# ade_7753.net
KiCad netlist of a schematic drawn in EAGLE
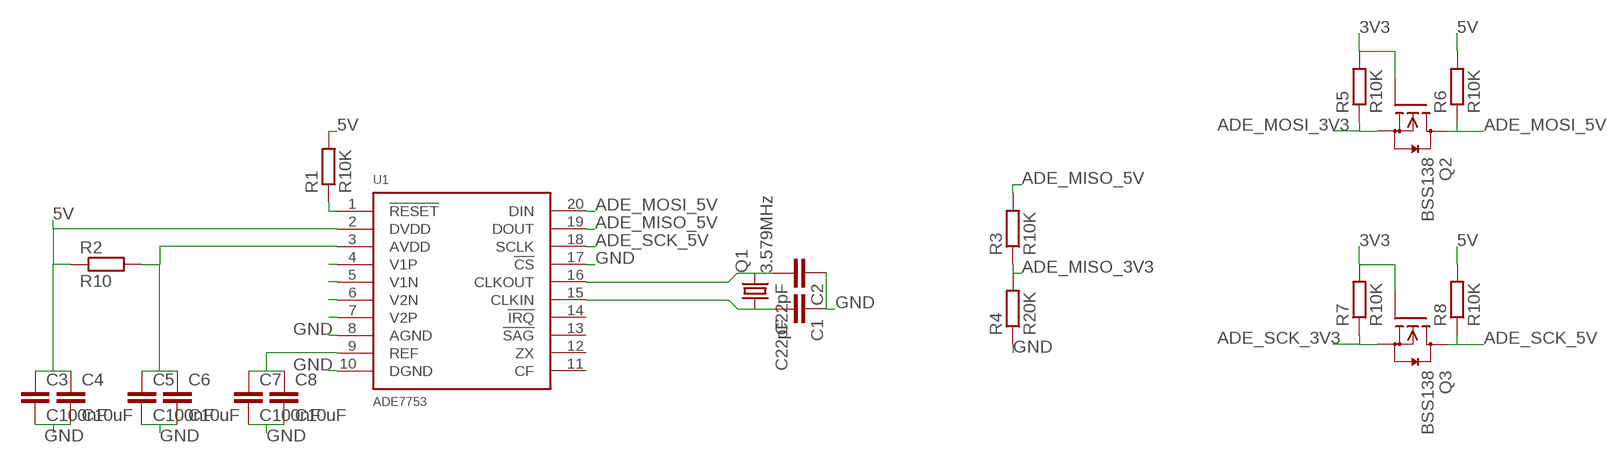
[diagram p0: schematic, sheet 1]

(export (version "E")
  (design (tool "Eeschema 10.0.6"))
  (components
    (comp (ref "C1")
      (value "C22pF")
      (footprint "eagle-import:C0805")
      (libsource (lib "eagle-import") (part "C-EUC0805"))
    )
    (comp (ref "C2")
      (value "C22pF")
      (footprint "eagle-import:C0805")
      (libsource (lib "eagle-import") (part "C-EUC0805"))
    )
    (comp (ref "C3")
      (value "C100nF")
      (footprint "eagle-import:C0805")
      (libsource (lib "eagle-import") (part "C-EUC0805"))
    )
    (comp (ref "C4")
      (value "C10uF")
      (footprint "eagle-import:C0805")
      (libsource (lib "eagle-import") (part "C-EUC0805"))
    )
    (comp (ref "C5")
      (value "C100nF")
      (footprint "eagle-import:C0805")
      (libsource (lib "eagle-import") (part "C-EUC0805"))
    )
    (comp (ref "C6")
      (value "C10uF")
      (footprint "eagle-import:C0805")
      (libsource (lib "eagle-import") (part "C-EUC0805"))
    )
    (comp (ref "C7")
      (value "C100nF")
      (footprint "eagle-import:C0805")
      (libsource (lib "eagle-import") (part "C-EUC0805"))
    )
    (comp (ref "C8")
      (value "C10uF")
      (footprint "eagle-import:C0805")
      (libsource (lib "eagle-import") (part "C-EUC0805"))
    )
    (comp (ref "Q1")
      (value "3.579MHz")
      (footprint "eagle-import:HC49_S")
      (libsource (lib "eagle-import") (part "CRYSTALHC49S"))
    )
    (comp (ref "Q2")
      (value "BSS138")
      (footprint "eagle-import:SOT23")
      (libsource (lib "eagle-import") (part "BSS138"))
    )
    (comp (ref "Q3")
      (value "BSS138")
      (footprint "eagle-import:SOT23")
      (libsource (lib "eagle-import") (part "BSS138"))
    )
    (comp (ref "R1")
      (value "R10K")
      (footprint "eagle-import:M0805")
      (libsource (lib "eagle-import") (part "R-EU_M0805"))
    )
    (comp (ref "R2")
      (value "R10")
      (footprint "eagle-import:M0805")
      (libsource (lib "eagle-import") (part "R-EU_M0805"))
    )
    (comp (ref "R3")
      (value "R10K")
      (footprint "eagle-import:M0805")
      (libsource (lib "eagle-import") (part "R-EU_M0805"))
    )
    (comp (ref "R4")
      (value "R20K")
      (footprint "eagle-import:M0805")
      (libsource (lib "eagle-import") (part "R-EU_M0805"))
    )
    (comp (ref "R5")
      (value "R10K")
      (footprint "eagle-import:M0805")
      (libsource (lib "eagle-import") (part "R-EU_M0805"))
    )
    (comp (ref "R6")
      (value "R10K")
      (footprint "eagle-import:M0805")
      (libsource (lib "eagle-import") (part "R-EU_M0805"))
    )
    (comp (ref "R7")
      (value "R10K")
      (footprint "eagle-import:M0805")
      (libsource (lib "eagle-import") (part "R-EU_M0805"))
    )
    (comp (ref "R8")
      (value "R10K")
      (footprint "eagle-import:M0805")
      (libsource (lib "eagle-import") (part "R-EU_M0805"))
    )
    (comp (ref "U1")
      (value "ADE7753")
      (footprint "eagle-import:SSOP-20")
      (libsource (lib "eagle-import") (part "ADE7753"))
    )
  )
  (nets
    (net (code "1") (name "/3V3") (class "Default")
      (node (ref "Q2") (pin "1") (pinfunction "G_1") (pintype "passive"))
      (node (ref "Q3") (pin "1") (pinfunction "G_1") (pintype "passive"))
      (node (ref "R5") (pin "2") (pinfunction "2_2") (pintype "passive"))
      (node (ref "R7") (pin "2") (pinfunction "2_2") (pintype "passive"))
    )
    (net (code "2") (name "/5V") (class "Default")
      (node (ref "C3") (pin "1") (pinfunction "1_1") (pintype "passive"))
      (node (ref "C4") (pin "1") (pinfunction "1_1") (pintype "passive"))
      (node (ref "R1") (pin "2") (pinfunction "2_2") (pintype "passive"))
      (node (ref "R2") (pin "1") (pinfunction "1_1") (pintype "passive"))
      (node (ref "R6") (pin "2") (pinfunction "2_2") (pintype "passive"))
      (node (ref "R8") (pin "2") (pinfunction "2_2") (pintype "passive"))
      (node (ref "U1") (pin "2") (pinfunction "DVDD_2") (pintype "bidirectional"))
    )
    (net (code "3") (name "/ADE_MISO_3V3") (class "Default")
      (node (ref "R3") (pin "1") (pinfunction "1_1") (pintype "passive"))
      (node (ref "R4") (pin "2") (pinfunction "2_2") (pintype "passive"))
    )
    (net (code "4") (name "/ADE_MISO_5V") (class "Default")
      (node (ref "R3") (pin "2") (pinfunction "2_2") (pintype "passive"))
      (node (ref "U1") (pin "19") (pinfunction "DOUT_19") (pintype "bidirectional"))
    )
    (net (code "5") (name "/ADE_MOSI_3V3") (class "Default")
      (node (ref "Q2") (pin "2") (pinfunction "S_2") (pintype "passive"))
      (node (ref "R5") (pin "1") (pinfunction "1_1") (pintype "passive"))
    )
    (net (code "6") (name "/ADE_MOSI_5V") (class "Default")
      (node (ref "Q2") (pin "3") (pinfunction "D_3") (pintype "passive"))
      (node (ref "R6") (pin "1") (pinfunction "1_1") (pintype "passive"))
      (node (ref "U1") (pin "20") (pinfunction "DIN_20") (pintype "bidirectional"))
    )
    (net (code "7") (name "/ADE_SCK_3V3") (class "Default")
      (node (ref "Q3") (pin "2") (pinfunction "S_2") (pintype "passive"))
      (node (ref "R7") (pin "1") (pinfunction "1_1") (pintype "passive"))
    )
    (net (code "8") (name "/ADE_SCK_5V") (class "Default")
      (node (ref "Q3") (pin "3") (pinfunction "D_3") (pintype "passive"))
      (node (ref "R8") (pin "1") (pinfunction "1_1") (pintype "passive"))
      (node (ref "U1") (pin "18") (pinfunction "SCLK_18") (pintype "bidirectional"))
    )
    (net (code "9") (name "/GND") (class "Default")
      (node (ref "C1") (pin "1") (pinfunction "1_1") (pintype "passive"))
      (node (ref "C2") (pin "1") (pinfunction "1_1") (pintype "passive"))
      (node (ref "C3") (pin "2") (pinfunction "2_2") (pintype "passive"))
      (node (ref "C4") (pin "2") (pinfunction "2_2") (pintype "passive"))
      (node (ref "C5") (pin "2") (pinfunction "2_2") (pintype "passive"))
      (node (ref "C6") (pin "2") (pinfunction "2_2") (pintype "passive"))
      (node (ref "C7") (pin "2") (pinfunction "2_2") (pintype "passive"))
      (node (ref "C8") (pin "2") (pinfunction "2_2") (pintype "passive"))
      (node (ref "R4") (pin "1") (pinfunction "1_1") (pintype "passive"))
      (node (ref "U1") (pin "10") (pinfunction "DGND_10") (pintype "bidirectional"))
      (node (ref "U1") (pin "17") (pinfunction "~{CS}_17") (pintype "bidirectional"))
      (node (ref "U1") (pin "8") (pinfunction "AGND_8") (pintype "bidirectional"))
    )
    (net (code "10") (name "Net-(U1-AVDD)") (class "Default")
      (node (ref "C5") (pin "1") (pinfunction "1_1") (pintype "passive"))
      (node (ref "C6") (pin "1") (pinfunction "1_1") (pintype "passive"))
      (node (ref "R2") (pin "2") (pinfunction "2_2") (pintype "passive"))
      (node (ref "U1") (pin "3") (pinfunction "AVDD_3") (pintype "bidirectional"))
    )
    (net (code "11") (name "Net-(U1-CLKIN)") (class "Default")
      (node (ref "C1") (pin "2") (pinfunction "2_2") (pintype "passive"))
      (node (ref "Q1") (pin "1") (pinfunction "1_1") (pintype "passive"))
      (node (ref "U1") (pin "15") (pinfunction "CLKIN_15") (pintype "bidirectional"))
    )
    (net (code "12") (name "Net-(U1-CLKOUT)") (class "Default")
      (node (ref "C2") (pin "2") (pinfunction "2_2") (pintype "passive"))
      (node (ref "Q1") (pin "2") (pinfunction "2_2") (pintype "passive"))
      (node (ref "U1") (pin "16") (pinfunction "CLKOUT_16") (pintype "bidirectional"))
    )
    (net (code "13") (name "Net-(U1-REF)") (class "Default")
      (node (ref "C7") (pin "1") (pinfunction "1_1") (pintype "passive"))
      (node (ref "C8") (pin "1") (pinfunction "1_1") (pintype "passive"))
      (node (ref "U1") (pin "9") (pinfunction "REF_9") (pintype "bidirectional"))
    )
    (net (code "14") (name "Net-(U1-~{RESET})") (class "Default")
      (node (ref "R1") (pin "1") (pinfunction "1_1") (pintype "passive"))
      (node (ref "U1") (pin "1") (pinfunction "~{RESET}_1") (pintype "bidirectional"))
    )
    (net (code "15") (name "unconnected-(U1-CF-Pad11)") (class "Default")
      (node (ref "U1") (pin "11") (pinfunction "CF_11") (pintype "bidirectional"))
    )
    (net (code "16") (name "unconnected-(U1-V1N-Pad5)") (class "Default")
      (node (ref "U1") (pin "5") (pinfunction "V1N_5") (pintype "bidirectional"))
    )
    (net (code "17") (name "unconnected-(U1-V1P-Pad4)") (class "Default")
      (node (ref "U1") (pin "4") (pinfunction "V1P_4") (pintype "bidirectional"))
    )
    (net (code "18") (name "unconnected-(U1-V2N-Pad6)") (class "Default")
      (node (ref "U1") (pin "6") (pinfunction "V2N_6") (pintype "bidirectional"))
    )
    (net (code "19") (name "unconnected-(U1-V2P-Pad7)") (class "Default")
      (node (ref "U1") (pin "7") (pinfunction "V2P_7") (pintype "bidirectional"))
    )
    (net (code "20") (name "unconnected-(U1-ZX-Pad12)") (class "Default")
      (node (ref "U1") (pin "12") (pinfunction "ZX_12") (pintype "bidirectional"))
    )
    (net (code "21") (name "unconnected-(U1-~{IRQ}-Pad14)") (class "Default")
      (node (ref "U1") (pin "14") (pinfunction "~{IRQ}_14") (pintype "bidirectional"))
    )
    (net (code "22") (name "unconnected-(U1-~{SAG}-Pad13)") (class "Default")
      (node (ref "U1") (pin "13") (pinfunction "~{SAG}_13") (pintype "bidirectional"))
    )
  )
)
